# Fonte_12V-2A.net
KiCad netlist of a schematic drawn in Altium Designer
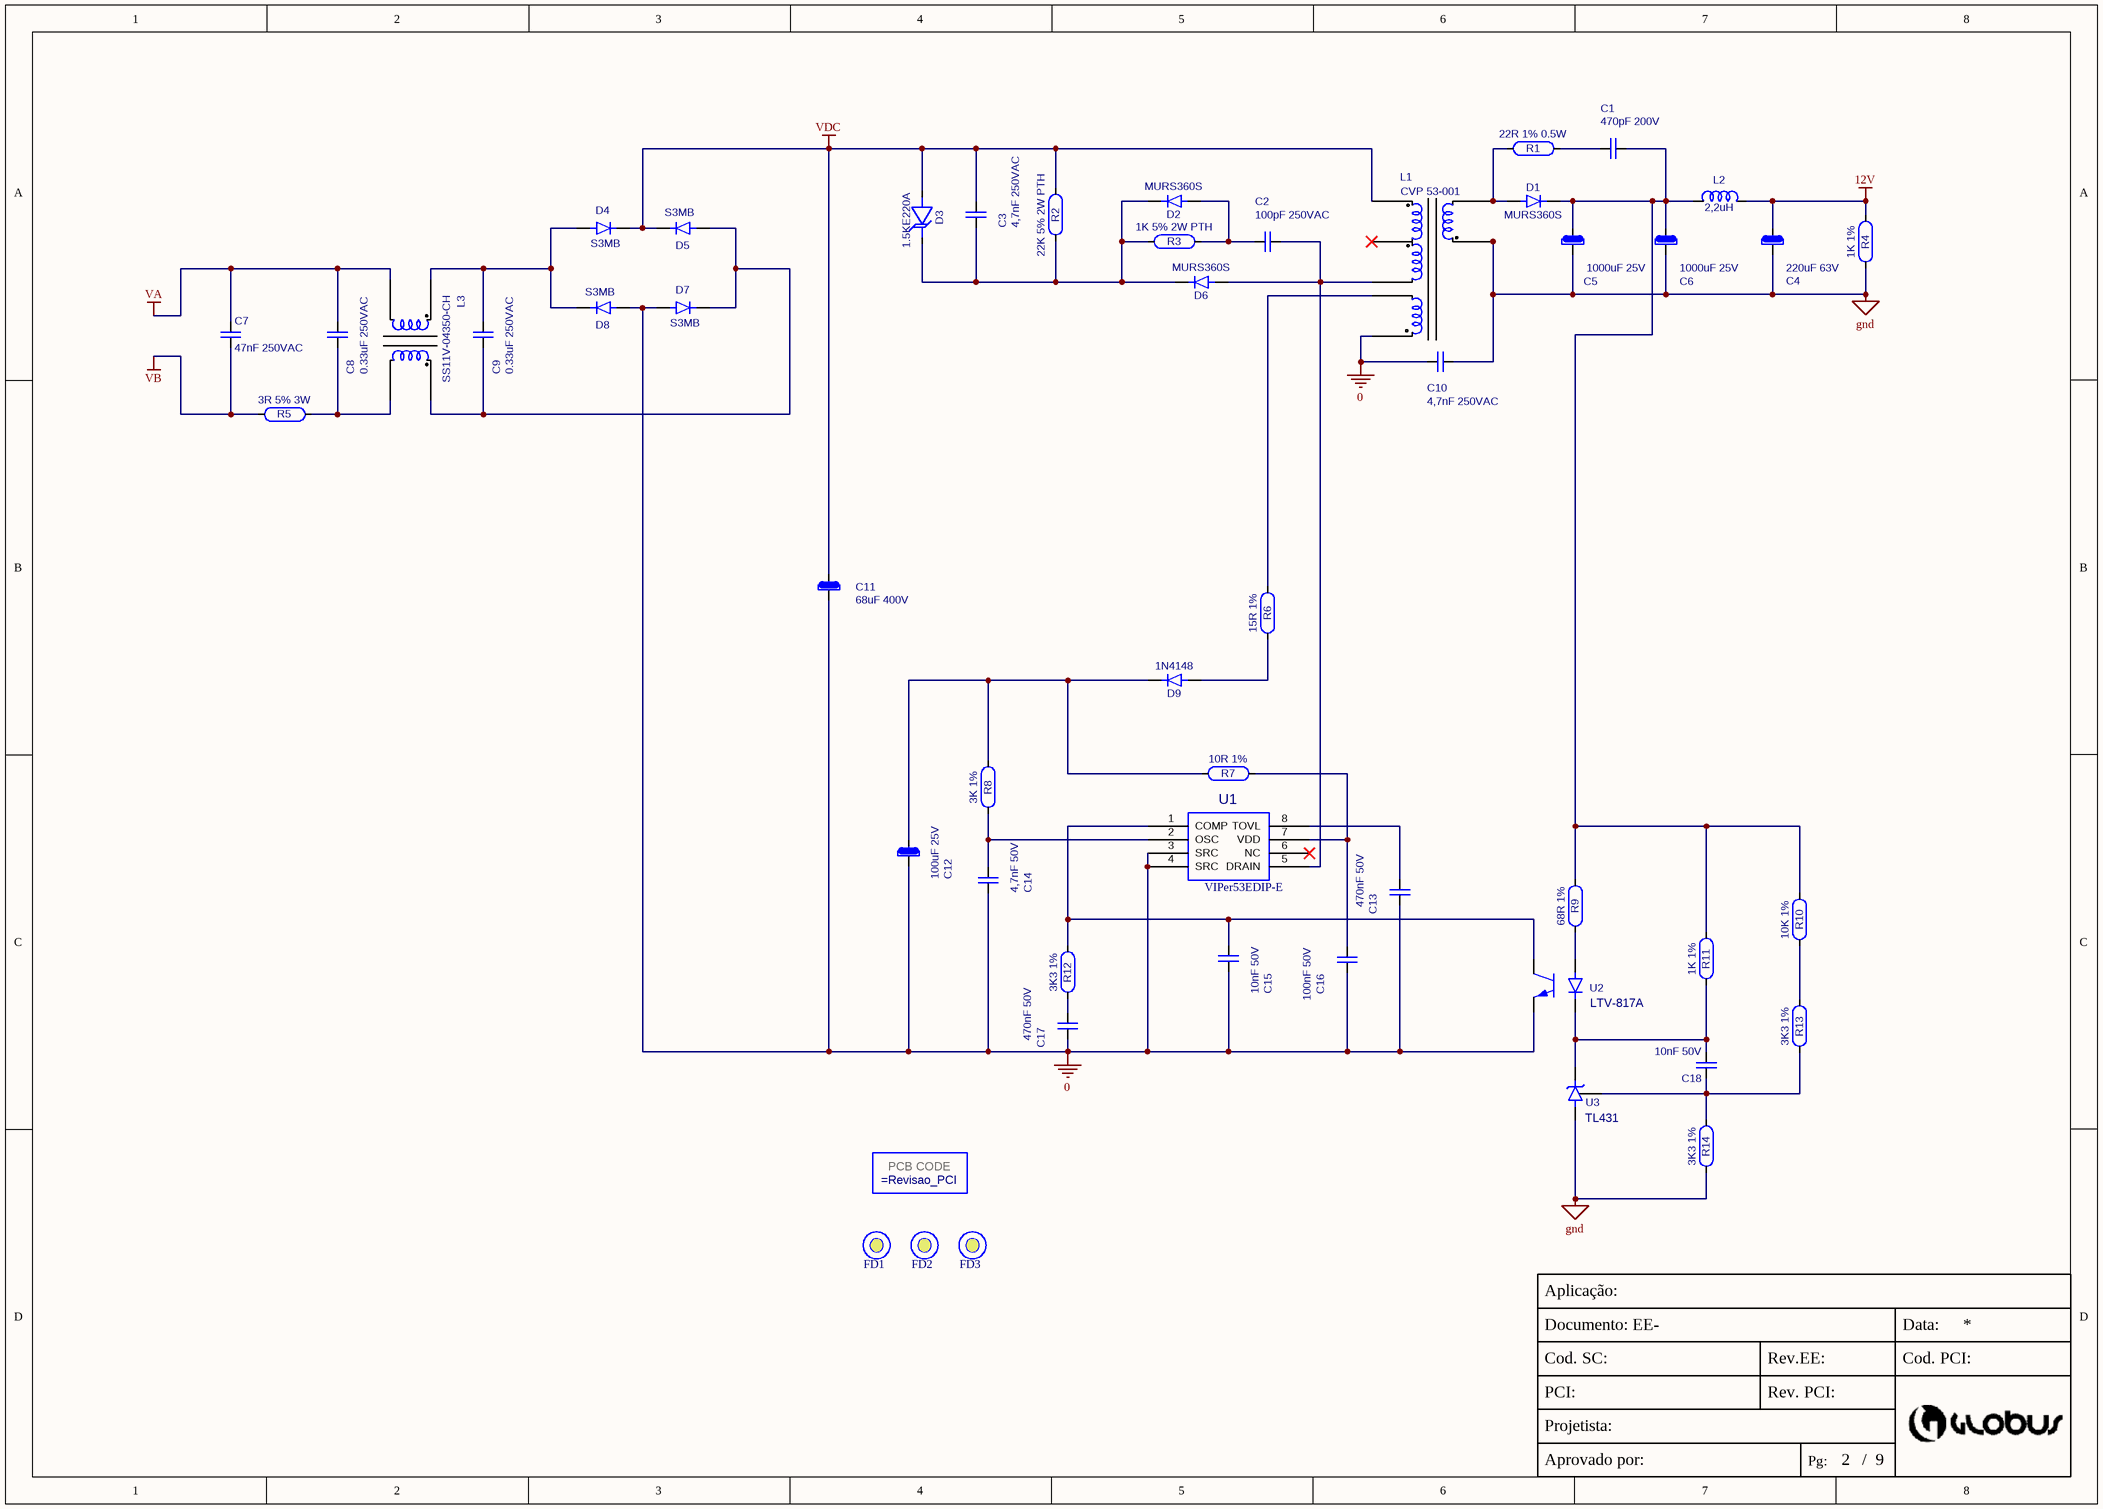
[diagram p0: Fonte 12V-2A.SchDoc]

(export (version "E")
  (design (tool "Eeschema 10.0.6"))
  (components
    (comp (ref "=Revisao_PCI")
      (value "*")
      (footprint "NULL_FOOTPRINT")
      (description "Preencher com o código da placa. Irá aparecer na serigrafia.")
      (libsource (lib "GLOBUS_ALTIUM") (part "CODIGO PCI"))
    )
    (comp (ref "C1")
      (value "470pF 200V")
      (footprint "C0603")
      (fields (field (name "PART NUMBER") "06032C471KAT2A"))
      (libsource (lib "GLOBUS_ALTIUM") (part "CC 470pF 200V 0603"))
    )
    (comp (ref "C2")
      (value "100pF 250VAC")
      (footprint "CAP_DE")
      (fields (field (name "PART NUMBER") "DE1B3KX101KA4BN01F"))
      (libsource (lib "GLOBUS_ALTIUM") (part "CC 100pF 250VAC"))
    )
    (comp (ref "C3")
      (value "4,7nF 250VAC")
      (footprint "WYO")
      (fields (field (name "PART NUMBER") "WYO472MCMCF0KR") (field (name "Comment") "4,7nF 250VAC Y2"))
      (libsource (lib "GLOBUS_ALTIUM") (part "CC 4,7nF 250VAC Y2"))
    )
    (comp (ref "C4")
      (value "220uF 63V")
      (footprint "CAP200P_D10H20")
      (description "C.Elet.220uF 63V 20% Radial")
      (libsource (lib "GLOBUS_ALTIUM") (part "CE 220uF 63V PTH"))
    )
    (comp (ref "C5")
      (value "1000uF 25V")
      (footprint "CAP5_D12.5H25")
      (description "C.Elet.1000uF 25V 20% Radial")
      (fields (field (name "PART NUMBER") "REA102M1EBK-1320P"))
      (libsource (lib "GLOBUS_ALTIUM") (part "CE 1000uF 25V PTH"))
    )
    (comp (ref "C6")
      (value "1000uF 25V")
      (footprint "CAP5_D12.5H25")
      (description "C.Elet.1000uF 25V 20% Radial")
      (fields (field (name "PART NUMBER") "REA102M1EBK-1320P"))
      (libsource (lib "GLOBUS_ALTIUM") (part "CE 1000uF 25V PTH"))
    )
    (comp (ref "C7")
      (value "47nF 250VAC")
      (footprint "CAP_R75_H11mm_L13mm")
      (fields (field (name "PART NUMBER") "R75LF24704000K"))
      (libsource (lib "GLOBUS_ALTIUM") (part "CC 47nF 250VAC"))
    )
    (comp (ref "C8")
      (value "0.33uF 250VAC")
      (footprint "R75")
      (fields (field (name "PART NUMBER") "ECQ-U2A334KL"))
      (libsource (lib "GLOBUS_ALTIUM") (part "CC 0.33uF 250VAC"))
    )
    (comp (ref "C9")
      (value "0.33uF 250VAC")
      (footprint "R75")
      (fields (field (name "PART NUMBER") "ECQ-U2A334KL"))
      (libsource (lib "GLOBUS_ALTIUM") (part "CC 0.33uF 250VAC"))
    )
    (comp (ref "C10")
      (value "4,7nF 250VAC")
      (footprint "WYO")
      (fields (field (name "PART NUMBER") "WYO472MCMCF0KR") (field (name "Comment") "4,7nF 250VAC Y2"))
      (libsource (lib "GLOBUS_ALTIUM") (part "CC 4,7nF 250VAC Y2"))
    )
    (comp (ref "C11")
      (value "68uF 400V")
      (footprint "CAP5_D12.5H31.5")
      (description "C.Elet.68uF 400V 20% Radial")
      (fields (field (name "PART NUMBER") "UPZ2G680MHD"))
      (libsource (lib "GLOBUS_ALTIUM") (part "CE 68uF 400V PTH"))
    )
    (comp (ref "C12")
      (value "100uF 25V")
      (footprint "CAP100P_D6.3H11")
      (description "C.Elet.1000uF 25V 20% Radial")
      (libsource (lib "GLOBUS_ALTIUM") (part "CE 100uF 25V PTH"))
    )
    (comp (ref "C13")
      (value "470nF 50V")
      (footprint "C0805")
      (libsource (lib "GLOBUS_ALTIUM") (part "CC 470nF 50V 0805"))
    )
    (comp (ref "C14")
      (value "4,7nF 50V")
      (footprint "C0805")
      (libsource (lib "GLOBUS_ALTIUM") (part "CC 4,7nF 50V 0805"))
    )
    (comp (ref "C15")
      (value "10nF 50V")
      (footprint "C0805")
      (libsource (lib "GLOBUS_ALTIUM") (part "CC 10nF 50V 0805"))
    )
    (comp (ref "C16")
      (value "100nF 50V")
      (footprint "C0805")
      (libsource (lib "GLOBUS_ALTIUM") (part "CC 100nF 50V 0805"))
    )
    (comp (ref "C17")
      (value "470nF 50V")
      (footprint "C0805")
      (libsource (lib "GLOBUS_ALTIUM") (part "CC 470nF 50V 0805"))
    )
    (comp (ref "C18")
      (value "10nF 50V")
      (footprint "C0805")
      (libsource (lib "GLOBUS_ALTIUM") (part "CC 10nF 50V 0805"))
    )
    (comp (ref "D1")
      (value "MURS360S")
      (footprint "DO214AA-SMB")
      (description "Dio.Ultra Fast Rectifier SMT 600V 3A SMC MURS360S")
      (libsource (lib "GLOBUS_ALTIUM") (part "D MURS360S SMB"))
    )
    (comp (ref "D2")
      (value "MURS360S")
      (footprint "DO214AA-SMB")
      (description "Dio.Ultra Fast Rectifier SMT 600V 3A SMC MURS360S")
      (libsource (lib "GLOBUS_ALTIUM") (part "D MURS360S SMB"))
    )
    (comp (ref "D3")
      (value "1.5KE220A")
      (footprint "1.5KE")
      (description "D 1.5KE220A 1.5KE")
      (fields (field (name "PART NUMBER") "{Part Number}"))
      (libsource (lib "GLOBUS_ALTIUM") (part "D 1.5KE220A 1.5KE"))
    )
    (comp (ref "D4")
      (value "S3MB")
      (footprint "DO214AA-SMB")
      (description "D S3MB DO214AA")
      (fields (field (name "PART NUMBER") "{Part Number}"))
      (libsource (lib "GLOBUS_ALTIUM") (part "D S3MB DO214AA"))
    )
    (comp (ref "D5")
      (value "S3MB")
      (footprint "DO214AA-SMB")
      (description "D S3MB DO214AA")
      (fields (field (name "PART NUMBER") "{Part Number}"))
      (libsource (lib "GLOBUS_ALTIUM") (part "D S3MB DO214AA"))
    )
    (comp (ref "D6")
      (value "MURS360S")
      (footprint "DO214AA-SMB")
      (description "Dio.Ultra Fast Rectifier SMT 600V 3A SMC MURS360S")
      (libsource (lib "GLOBUS_ALTIUM") (part "D MURS360S SMB"))
    )
    (comp (ref "D7")
      (value "S3MB")
      (footprint "DO214AA-SMB")
      (description "D S3MB DO214AA")
      (fields (field (name "PART NUMBER") "{Part Number}"))
      (libsource (lib "GLOBUS_ALTIUM") (part "D S3MB DO214AA"))
    )
    (comp (ref "D8")
      (value "S3MB")
      (footprint "DO214AA-SMB")
      (description "D S3MB DO214AA")
      (fields (field (name "PART NUMBER") "{Part Number}"))
      (libsource (lib "GLOBUS_ALTIUM") (part "D S3MB DO214AA"))
    )
    (comp (ref "D9")
      (value "1N4148")
      (footprint "SOD80-MINIMELF")
      (description "Diodo 1N4148 (LL4148) MINI MELF/SOD80")
      (libsource (lib "GLOBUS_ALTIUM") (part "D 1N4148 SMD"))
    )
    (comp (ref "FD1")
      (value "Fiducial")
      (footprint "Fiducial")
      (libsource (lib "GLOBUS_ALTIUM") (part "Fiducial"))
    )
    (comp (ref "FD2")
      (value "Fiducial")
      (footprint "Fiducial")
      (libsource (lib "GLOBUS_ALTIUM") (part "Fiducial"))
    )
    (comp (ref "FD3")
      (value "Fiducial")
      (footprint "Fiducial")
      (libsource (lib "GLOBUS_ALTIUM") (part "Fiducial"))
    )
    (comp (ref "L1")
      (value "CVP 53-001")
      (footprint "CVP 53-001")
      (description "IND CVP 53-001")
      (libsource (lib "GLOBUS_ALTIUM") (part "IND CVP 53-001"))
    )
    (comp (ref "L2")
      (value "2,2uH")
      (footprint "l2512")
      (description "IND 2,2uH 2512 SMD")
      (fields (field (name "PART NUMBER") "SRN2512-2R2M"))
      (libsource (lib "GLOBUS_ALTIUM") (part "IND 2,2uH 2512 SMD"))
    )
    (comp (ref "L3")
      (value "SS11V-04350-CH")
      (footprint "SS11V-04350-CH")
      (description "IND SS11V-04350-CH CHOKE PTH")
      (libsource (lib "GLOBUS_ALTIUM") (part "IND SS11V-04350-CH CHOKE PTH"))
    )
    (comp (ref "R1")
      (value "22R 1% 0.5W")
      (footprint "R0805")
      (description "RES 22R 1% 0805 0.5W")
      (fields (field (name "PART NUMBER") "ERJ-P06F22R0V") (field (name "Comment") "22R 1%"))
      (libsource (lib "GLOBUS_ALTIUM") (part "RES 22R 1% 0805 0.5W"))
    )
    (comp (ref "R2")
      (value "22K 5% 2W PTH")
      (footprint "RES2W_L16mm_D5.5")
      (description "RES 22K 5% 2W PTH")
      (fields (field (name "PART NUMBER") "ON2235E-R58") (field (name "Comment") "22K 5% 2W"))
      (libsource (lib "GLOBUS_ALTIUM") (part "RES 22K 5% 2W PTH"))
    )
    (comp (ref "R3")
      (value "1K 5% 2W PTH")
      (footprint "RES2W_L16mm_D5.5")
      (description "RES 1K 5% 2W PTH")
      (fields (field (name "PART NUMBER") "ON1025E-R58") (field (name "Comment") "1K 5% 2W"))
      (libsource (lib "GLOBUS_ALTIUM") (part "RES 1K 5% 2W PTH"))
    )
    (comp (ref "R4")
      (value "1K 1%")
      (footprint "R1206")
      (description "RES 1K 1% 1206")
      (fields (field (name "PART NUMBER") "{Part Number}"))
      (libsource (lib "GLOBUS_ALTIUM") (part "RES 1K 1% 1206"))
    )
    (comp (ref "R5")
      (value "3R 5% 3W")
      (footprint "RES2W_L16mm_D5.5")
      (description "RES 3R 5% 3W PTH")
      (fields (field (name "PART NUMBER") "PR03000203008JAC00"))
      (libsource (lib "GLOBUS_ALTIUM") (part "RES 3R 5% 3W PTH"))
    )
    (comp (ref "R6")
      (value "15R 1%")
      (footprint "R1206")
      (description "RES 15R 1% 1206")
      (fields (field (name "PART NUMBER") "{Part Number}"))
      (libsource (lib "GLOBUS_ALTIUM") (part "RES 15R 1% 1206"))
    )
    (comp (ref "R7")
      (value "10R 1%")
      (footprint "R0805")
      (description "RES 10R 1% 0805")
      (fields (field (name "PART NUMBER") "{Part Number}"))
      (libsource (lib "GLOBUS_ALTIUM") (part "RES 10R 1% 0805"))
    )
    (comp (ref "R8")
      (value "3K 1%")
      (footprint "R0805")
      (description "RES 3K 1% 0805")
      (fields (field (name "PART NUMBER") "{Part Number}"))
      (libsource (lib "GLOBUS_ALTIUM") (part "RES 3K 1% 0805"))
    )
    (comp (ref "R9")
      (value "68R 1%")
      (footprint "R1206")
      (description "RES 68R 1% 1206")
      (fields (field (name "PART NUMBER") "{Part Number}"))
      (libsource (lib "GLOBUS_ALTIUM") (part "RES 68R1% 1206"))
    )
    (comp (ref "R10")
      (value "10K 1%")
      (footprint "R0805")
      (description "RES 10K 1% 0805")
      (fields (field (name "PART NUMBER") "{Part Number}"))
      (libsource (lib "GLOBUS_ALTIUM") (part "RES 10K 1% 0805"))
    )
    (comp (ref "R11")
      (value "1K 1%")
      (footprint "R1206")
      (description "RES 1K 1% 1206")
      (fields (field (name "PART NUMBER") "{Part Number}"))
      (libsource (lib "GLOBUS_ALTIUM") (part "RES 1K 1% 1206"))
    )
    (comp (ref "R12")
      (value "3K3 1%")
      (footprint "R0805")
      (description "RES 3K3 1% 0805")
      (fields (field (name "PART NUMBER") "{Part Number}"))
      (libsource (lib "GLOBUS_ALTIUM") (part "RES 3K3 1% 0805"))
    )
    (comp (ref "R13")
      (value "3K3 1%")
      (footprint "R0805")
      (description "RES 3K3 1% 0805")
      (fields (field (name "PART NUMBER") "{Part Number}"))
      (libsource (lib "GLOBUS_ALTIUM") (part "RES 3K3 1% 0805"))
    )
    (comp (ref "R14")
      (value "3K3 1%")
      (footprint "R0805")
      (description "RES 3K3 1% 0805")
      (fields (field (name "PART NUMBER") "{Part Number}"))
      (libsource (lib "GLOBUS_ALTIUM") (part "RES 3K3 1% 0805"))
    )
    (comp (ref "U1")
      (value "VIPer53EDIP-E")
      (footprint "DIP8")
      (description "CI VIPer53E DIP-8")
      (fields (field (name "PART NUMBER") "{Part Number}"))
      (libsource (lib "GLOBUS_ALTIUM") (part "CI VIPer53E DIP-8"))
    )
    (comp (ref "U2")
      (value "LTV-817A")
      (footprint "DIP4")
      (description "CI LTV-817A DIP4")
      (libsource (lib "GLOBUS_ALTIUM") (part "CI LTV-817A DIP4"))
    )
    (comp (ref "U3")
      (value "TL431")
      (footprint "SOT23")
      (description "CI TL431 SOT23")
      (fields (field (name "PART NUMBER") "TL431AIL3T"))
      (libsource (lib "GLOBUS_ALTIUM") (part "CI TL431 SOT23"))
    )
  )
  (nets
    (net (code "1") (name "0") (class "Default")
      (node (ref "C10") (pin "1") (pinfunction "1_1") (pintype "passive"))
      (node (ref "C11") (pin "1") (pinfunction "negative_1") (pintype "passive"))
      (node (ref "C12") (pin "1") (pinfunction "negative_1") (pintype "passive"))
      (node (ref "C13") (pin "1") (pinfunction "1_1") (pintype "passive"))
      (node (ref "C14") (pin "2") (pinfunction "2_2") (pintype "passive"))
      (node (ref "C15") (pin "1") (pinfunction "1_1") (pintype "passive"))
      (node (ref "C16") (pin "1") (pinfunction "1_1") (pintype "passive"))
      (node (ref "C17") (pin "1") (pinfunction "1_1") (pintype "passive"))
      (node (ref "D7") (pin "1") (pinfunction "anode_1") (pintype "passive"))
      (node (ref "D8") (pin "1") (pinfunction "anode_1") (pintype "passive"))
      (node (ref "L1") (pin "2") (pinfunction "2_2") (pintype "passive"))
      (node (ref "U1") (pin "3") (pinfunction "SRC_3") (pintype "passive"))
      (node (ref "U1") (pin "4") (pinfunction "SRC_4") (pintype "passive"))
      (node (ref "U2") (pin "3") (pinfunction "E_3") (pintype "passive"))
    )
    (net (code "2") (name "12V") (class "Default")
      (node (ref "C4") (pin "2") (pinfunction "positive_2") (pintype "passive"))
      (node (ref "L2") (pin "2") (pinfunction "2_2") (pintype "passive"))
      (node (ref "R4") (pin "2") (pinfunction "2_2") (pintype "passive"))
    )
    (net (code "3") (name "Net-(C1-Pad1)") (class "Default")
      (node (ref "C1") (pin "1") (pinfunction "1_1") (pintype "passive"))
      (node (ref "R1") (pin "2") (pinfunction "2_2") (pintype "passive"))
    )
    (net (code "4") (name "Net-(C5-positive)") (class "Default")
      (node (ref "C1") (pin "2") (pinfunction "2_2") (pintype "passive"))
      (node (ref "C5") (pin "2") (pinfunction "positive_2") (pintype "passive"))
      (node (ref "C6") (pin "2") (pinfunction "positive_2") (pintype "passive"))
      (node (ref "D1") (pin "2") (pinfunction "K_2") (pintype "passive"))
      (node (ref "L2") (pin "1") (pinfunction "1_1") (pintype "passive"))
      (node (ref "R10") (pin "2") (pinfunction "2_2") (pintype "passive"))
      (node (ref "R11") (pin "2") (pinfunction "2_2") (pintype "passive"))
      (node (ref "R9") (pin "2") (pinfunction "2_2") (pintype "passive"))
    )
    (net (code "5") (name "Net-(C8-Pad2)") (class "Default")
      (node (ref "C8") (pin "2") (pinfunction "2_2") (pintype "passive"))
      (node (ref "L3") (pin "3") (pinfunction "3_3") (pintype "passive"))
      (node (ref "R5") (pin "2") (pinfunction "2_2") (pintype "passive"))
    )
    (net (code "6") (name "Net-(C12-positive)") (class "Default")
      (node (ref "C12") (pin "2") (pinfunction "positive_2") (pintype "passive"))
      (node (ref "D9") (pin "2") (pinfunction "cathode_2") (pintype "passive"))
      (node (ref "R7") (pin "1") (pinfunction "1_1") (pintype "passive"))
      (node (ref "R8") (pin "2") (pinfunction "2_2") (pintype "passive"))
    )
    (net (code "7") (name "Net-(C17-Pad2)") (class "Default")
      (node (ref "C17") (pin "2") (pinfunction "2_2") (pintype "passive"))
      (node (ref "R12") (pin "1") (pinfunction "1_1") (pintype "passive"))
    )
    (net (code "8") (name "Net-(D1-A)") (class "Default")
      (node (ref "D1") (pin "1") (pinfunction "A_1") (pintype "passive"))
      (node (ref "L1") (pin "10") (pinfunction "10_10") (pintype "passive"))
      (node (ref "L1") (pin "11") (pinfunction "11_11") (pintype "passive"))
      (node (ref "L1") (pin "9") (pinfunction "9_9") (pintype "passive"))
      (node (ref "R1") (pin "1") (pinfunction "1_1") (pintype "passive"))
    )
    (net (code "9") (name "Net-(D2-A)") (class "Default")
      (node (ref "C2") (pin "1") (pinfunction "1_1") (pintype "passive"))
      (node (ref "D2") (pin "1") (pinfunction "A_1") (pintype "passive"))
      (node (ref "R3") (pin "2") (pinfunction "2_2") (pintype "passive"))
    )
    (net (code "10") (name "Net-(D2-K)") (class "Default")
      (node (ref "C3") (pin "1") (pinfunction "1_1") (pintype "passive"))
      (node (ref "D2") (pin "2") (pinfunction "K_2") (pintype "passive"))
      (node (ref "D3") (pin "2") (pinfunction "cathode_2") (pintype "passive"))
      (node (ref "D6") (pin "2") (pinfunction "K_2") (pintype "passive"))
      (node (ref "R2") (pin "1") (pinfunction "1_1") (pintype "passive"))
      (node (ref "R3") (pin "1") (pinfunction "1_1") (pintype "passive"))
    )
    (net (code "11") (name "Net-(D4-anode)") (class "Default")
      (node (ref "C9") (pin "1") (pinfunction "1_1") (pintype "passive"))
      (node (ref "D4") (pin "1") (pinfunction "anode_1") (pintype "passive"))
      (node (ref "D8") (pin "2") (pinfunction "cathode_2") (pintype "passive"))
      (node (ref "L3") (pin "2") (pinfunction "2_2") (pintype "passive"))
    )
    (net (code "12") (name "Net-(D5-anode)") (class "Default")
      (node (ref "C9") (pin "2") (pinfunction "2_2") (pintype "passive"))
      (node (ref "D5") (pin "1") (pinfunction "anode_1") (pintype "passive"))
      (node (ref "D7") (pin "2") (pinfunction "cathode_2") (pintype "passive"))
      (node (ref "L3") (pin "1") (pinfunction "1_1") (pintype "passive"))
    )
    (net (code "13") (name "Net-(D6-A)") (class "Default")
      (node (ref "C2") (pin "2") (pinfunction "2_2") (pintype "passive"))
      (node (ref "D6") (pin "1") (pinfunction "A_1") (pintype "passive"))
      (node (ref "L1") (pin "3") (pinfunction "3_3") (pintype "passive"))
      (node (ref "U1") (pin "5") (pinfunction "DRAIN_5") (pintype "passive"))
    )
    (net (code "14") (name "Net-(D9-anode)") (class "Default")
      (node (ref "D9") (pin "1") (pinfunction "anode_1") (pintype "passive"))
      (node (ref "R6") (pin "1") (pinfunction "1_1") (pintype "passive"))
    )
    (net (code "15") (name "Net-(L1-Pad1)") (class "Default")
      (node (ref "L1") (pin "1") (pinfunction "1_1") (pintype "passive"))
      (node (ref "R6") (pin "2") (pinfunction "2_2") (pintype "passive"))
    )
    (net (code "16") (name "Net-(R10-Pad1)") (class "Default")
      (node (ref "R10") (pin "1") (pinfunction "1_1") (pintype "passive"))
      (node (ref "R13") (pin "2") (pinfunction "2_2") (pintype "passive"))
    )
    (net (code "17") (name "Net-(U1-COMP)") (class "Default")
      (node (ref "C15") (pin "2") (pinfunction "2_2") (pintype "passive"))
      (node (ref "R12") (pin "2") (pinfunction "2_2") (pintype "passive"))
      (node (ref "U1") (pin "1") (pinfunction "COMP_1") (pintype "passive"))
      (node (ref "U2") (pin "4") (pinfunction "C_4") (pintype "passive"))
    )
    (net (code "18") (name "Net-(U1-OSC)") (class "Default")
      (node (ref "C14") (pin "1") (pinfunction "1_1") (pintype "passive"))
      (node (ref "R8") (pin "1") (pinfunction "1_1") (pintype "passive"))
      (node (ref "U1") (pin "2") (pinfunction "OSC_2") (pintype "passive"))
    )
    (net (code "19") (name "Net-(U1-TOVL)") (class "Default")
      (node (ref "C13") (pin "2") (pinfunction "2_2") (pintype "passive"))
      (node (ref "U1") (pin "8") (pinfunction "TOVL_8") (pintype "passive"))
    )
    (net (code "20") (name "Net-(U1-VDD)") (class "Default")
      (node (ref "C16") (pin "2") (pinfunction "2_2") (pintype "passive"))
      (node (ref "R7") (pin "2") (pinfunction "2_2") (pintype "passive"))
      (node (ref "U1") (pin "7") (pinfunction "VDD_7") (pintype "passive"))
    )
    (net (code "21") (name "Net-(U2-A)") (class "Default")
      (node (ref "R9") (pin "1") (pinfunction "1_1") (pintype "passive"))
      (node (ref "U2") (pin "1") (pinfunction "A_1") (pintype "passive"))
    )
    (net (code "22") (name "Net-(U2-K)") (class "Default")
      (node (ref "C18") (pin "2") (pinfunction "2_2") (pintype "passive"))
      (node (ref "R11") (pin "1") (pinfunction "1_1") (pintype "passive"))
      (node (ref "U2") (pin "2") (pinfunction "K_2") (pintype "passive"))
      (node (ref "U3") (pin "1") (pinfunction "K_1") (pintype "passive"))
    )
    (net (code "23") (name "Net-(U3-F)") (class "Default")
      (node (ref "C18") (pin "1") (pinfunction "1_1") (pintype "passive"))
      (node (ref "R13") (pin "1") (pinfunction "1_1") (pintype "passive"))
      (node (ref "R14") (pin "2") (pinfunction "2_2") (pintype "passive"))
      (node (ref "U3") (pin "3") (pinfunction "F_3") (pintype "passive"))
    )
    (net (code "24") (name "VA") (class "Default")
      (node (ref "C7") (pin "1") (pinfunction "1_1") (pintype "passive"))
      (node (ref "C8") (pin "1") (pinfunction "1_1") (pintype "passive"))
      (node (ref "L3") (pin "4") (pinfunction "4_4") (pintype "passive"))
    )
    (net (code "25") (name "VB") (class "Default")
      (node (ref "C7") (pin "2") (pinfunction "2_2") (pintype "passive"))
      (node (ref "R5") (pin "1") (pinfunction "1_1") (pintype "passive"))
    )
    (net (code "26") (name "VDC") (class "Default")
      (node (ref "C11") (pin "2") (pinfunction "positive_2") (pintype "passive"))
      (node (ref "C3") (pin "2") (pinfunction "2_2") (pintype "passive"))
      (node (ref "D3") (pin "1") (pinfunction "anode_1") (pintype "passive"))
      (node (ref "D4") (pin "2") (pinfunction "cathode_2") (pintype "passive"))
      (node (ref "D5") (pin "2") (pinfunction "cathode_2") (pintype "passive"))
      (node (ref "L1") (pin "5") (pinfunction "5_5") (pintype "passive"))
      (node (ref "R2") (pin "2") (pinfunction "2_2") (pintype "passive"))
    )
    (net (code "27") (name "gnd") (class "Default")
      (node (ref "C10") (pin "2") (pinfunction "2_2") (pintype "passive"))
      (node (ref "C4") (pin "1") (pinfunction "negative_1") (pintype "passive"))
      (node (ref "C5") (pin "1") (pinfunction "negative_1") (pintype "passive"))
      (node (ref "C6") (pin "1") (pinfunction "negative_1") (pintype "passive"))
      (node (ref "L1") (pin "6") (pinfunction "6_6") (pintype "passive"))
      (node (ref "L1") (pin "7") (pinfunction "7_7") (pintype "passive"))
      (node (ref "L1") (pin "8") (pinfunction "8_8") (pintype "passive"))
      (node (ref "R14") (pin "1") (pinfunction "1_1") (pintype "passive"))
      (node (ref "R4") (pin "1") (pinfunction "1_1") (pintype "passive"))
      (node (ref "U3") (pin "2") (pinfunction "A_2") (pintype "passive"))
    )
    (net (code "28") (name "unconnected-(L1-Pad4)") (class "Default")
      (node (ref "L1") (pin "4") (pinfunction "4_4") (pintype "passive+no_connect"))
    )
    (net (code "29") (name "unconnected-(U1-NC-Pad6)") (class "Default")
      (node (ref "U1") (pin "6") (pinfunction "NC_6") (pintype "passive+no_connect"))
    )
  )
)
